# PLC_NPN-16.net
KiCad netlist of a schematic drawn in Altium Designer
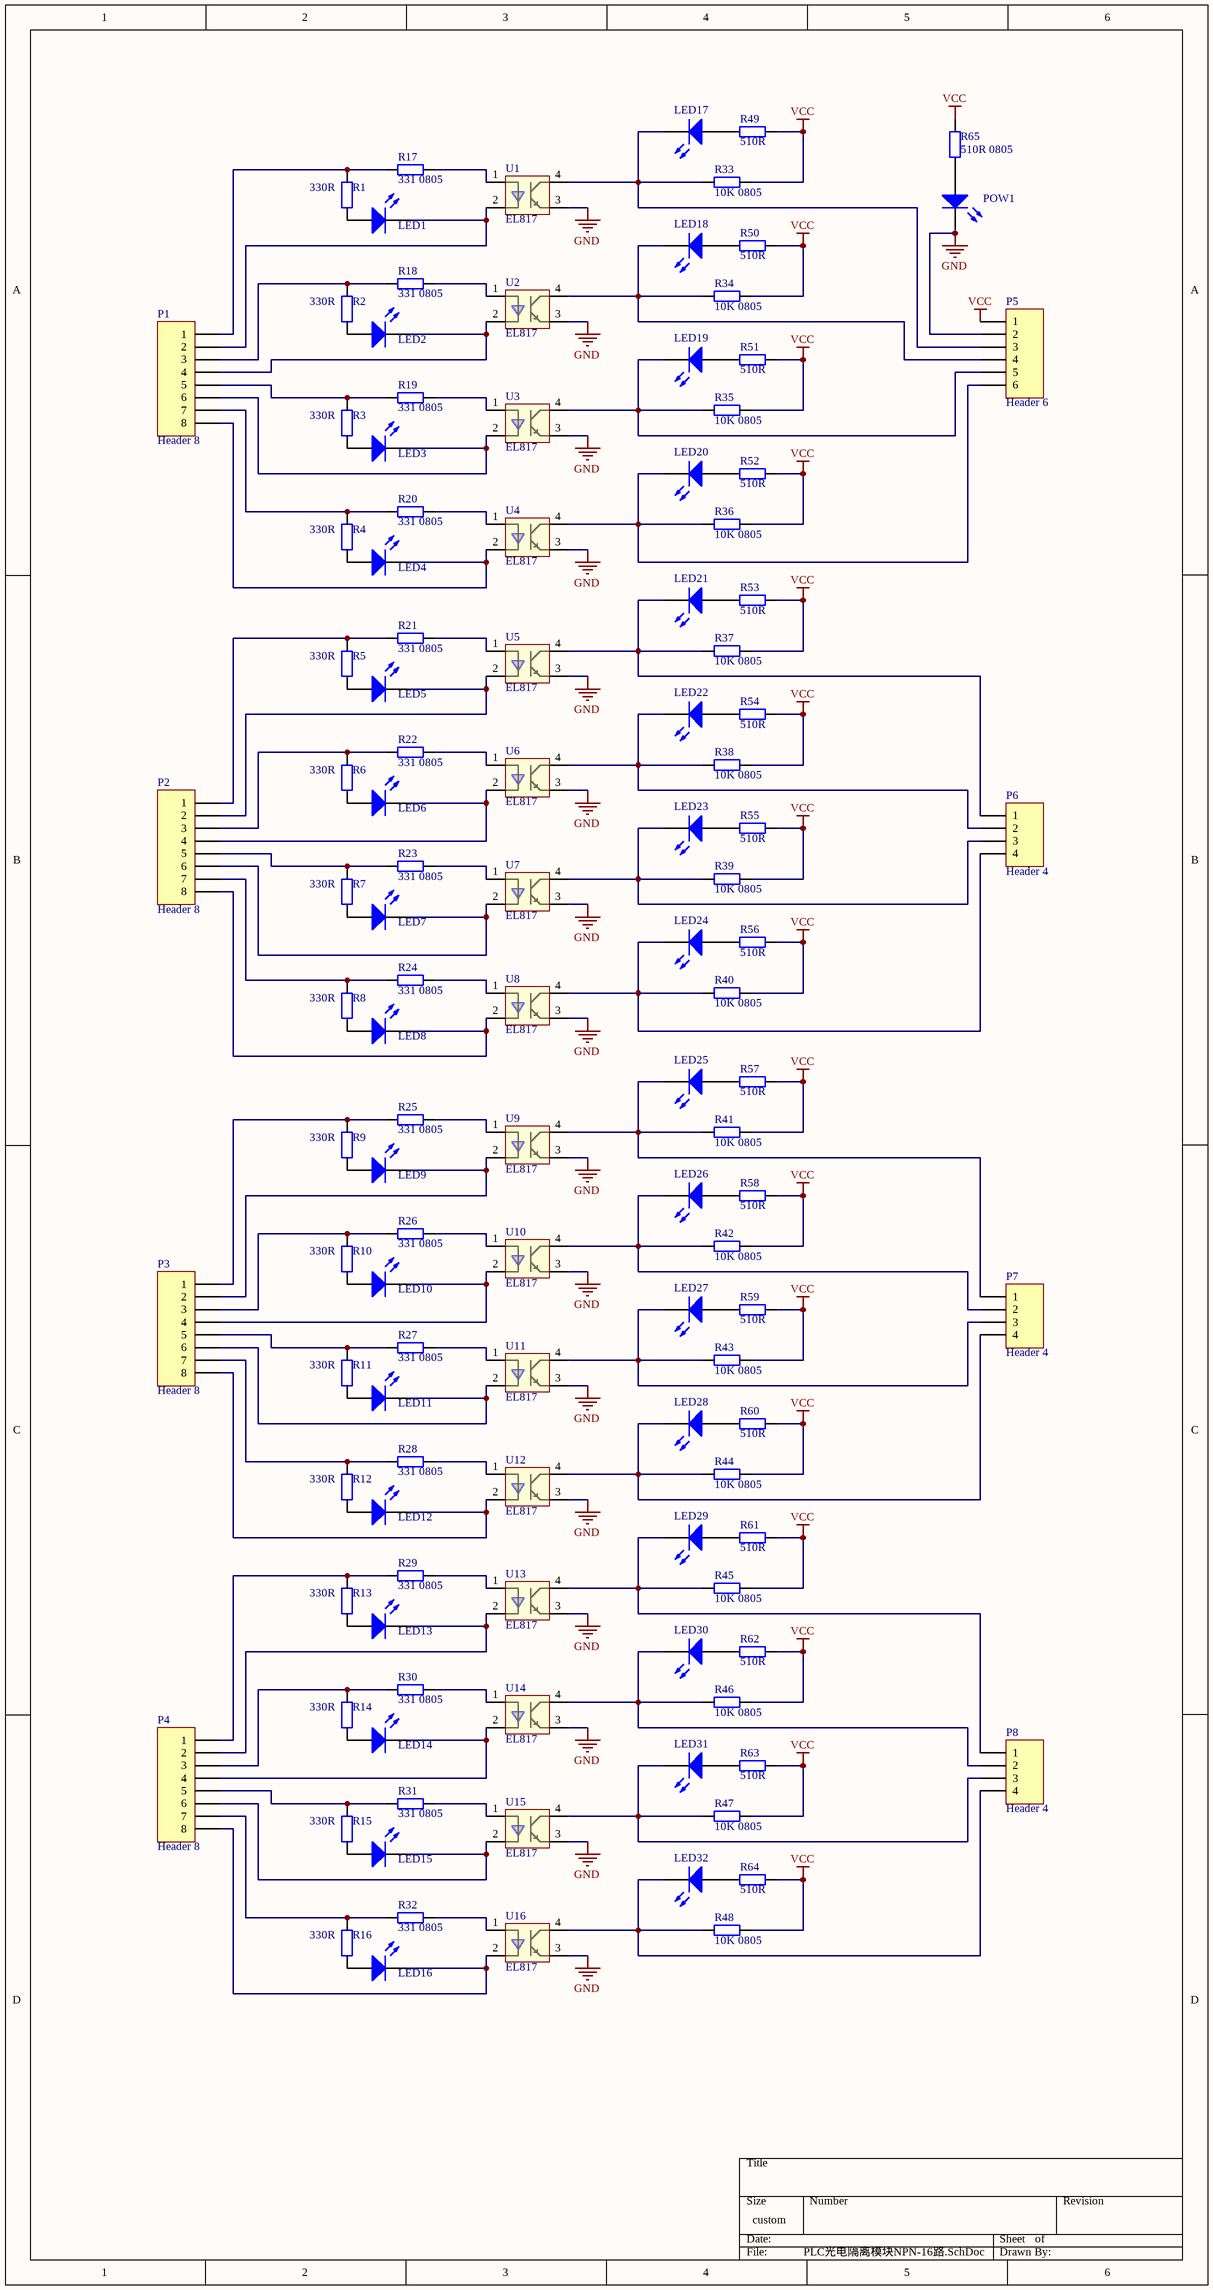
[diagram p0: PLC光电隔离模块NPN-16路.SchDoc]

(export (version "E")
  (design (tool "Eeschema 10.0.6"))
  (components
    (comp (ref "LED1")
      (value "0805")
      (footprint "LC-0805")
      (description "Typical INFRARED GaAs LED")
      (fields (field (name "PUBLISHER") "Altium Limited"))
      (libsource (lib "Miscellaneous Devices") (part "LED0"))
    )
    (comp (ref "LED2")
      (value "0805")
      (footprint "LC-0805")
      (description "Typical INFRARED GaAs LED")
      (fields (field (name "PUBLISHER") "Altium Limited"))
      (libsource (lib "Miscellaneous Devices") (part "LED0"))
    )
    (comp (ref "LED3")
      (value "0805")
      (footprint "LC-0805")
      (description "Typical INFRARED GaAs LED")
      (fields (field (name "PUBLISHER") "Altium Limited"))
      (libsource (lib "Miscellaneous Devices") (part "LED0"))
    )
    (comp (ref "LED4")
      (value "0805")
      (footprint "LC-0805")
      (description "Typical INFRARED GaAs LED")
      (fields (field (name "PUBLISHER") "Altium Limited"))
      (libsource (lib "Miscellaneous Devices") (part "LED0"))
    )
    (comp (ref "LED5")
      (value "0805")
      (footprint "LC-0805")
      (description "Typical INFRARED GaAs LED")
      (fields (field (name "PUBLISHER") "Altium Limited"))
      (libsource (lib "Miscellaneous Devices") (part "LED0"))
    )
    (comp (ref "LED6")
      (value "0805")
      (footprint "LC-0805")
      (description "Typical INFRARED GaAs LED")
      (fields (field (name "PUBLISHER") "Altium Limited"))
      (libsource (lib "Miscellaneous Devices") (part "LED0"))
    )
    (comp (ref "LED7")
      (value "0805")
      (footprint "LC-0805")
      (description "Typical INFRARED GaAs LED")
      (fields (field (name "PUBLISHER") "Altium Limited"))
      (libsource (lib "Miscellaneous Devices") (part "LED0"))
    )
    (comp (ref "LED8")
      (value "0805")
      (footprint "LC-0805")
      (description "Typical INFRARED GaAs LED")
      (fields (field (name "PUBLISHER") "Altium Limited"))
      (libsource (lib "Miscellaneous Devices") (part "LED0"))
    )
    (comp (ref "LED9")
      (value "0805")
      (footprint "LC-0805")
      (description "Typical INFRARED GaAs LED")
      (fields (field (name "PUBLISHER") "Altium Limited"))
      (libsource (lib "Miscellaneous Devices") (part "LED0"))
    )
    (comp (ref "LED10")
      (value "0805")
      (footprint "LC-0805")
      (description "Typical INFRARED GaAs LED")
      (fields (field (name "PUBLISHER") "Altium Limited"))
      (libsource (lib "Miscellaneous Devices") (part "LED0"))
    )
    (comp (ref "LED11")
      (value "0805")
      (footprint "LC-0805")
      (description "Typical INFRARED GaAs LED")
      (fields (field (name "PUBLISHER") "Altium Limited"))
      (libsource (lib "Miscellaneous Devices") (part "LED0"))
    )
    (comp (ref "LED12")
      (value "0805")
      (footprint "LC-0805")
      (description "Typical INFRARED GaAs LED")
      (fields (field (name "PUBLISHER") "Altium Limited"))
      (libsource (lib "Miscellaneous Devices") (part "LED0"))
    )
    (comp (ref "LED13")
      (value "0805")
      (footprint "LC-0805")
      (description "Typical INFRARED GaAs LED")
      (fields (field (name "PUBLISHER") "Altium Limited"))
      (libsource (lib "Miscellaneous Devices") (part "LED0"))
    )
    (comp (ref "LED14")
      (value "0805")
      (footprint "LC-0805")
      (description "Typical INFRARED GaAs LED")
      (fields (field (name "PUBLISHER") "Altium Limited"))
      (libsource (lib "Miscellaneous Devices") (part "LED0"))
    )
    (comp (ref "LED15")
      (value "0805")
      (footprint "LC-0805")
      (description "Typical INFRARED GaAs LED")
      (fields (field (name "PUBLISHER") "Altium Limited"))
      (libsource (lib "Miscellaneous Devices") (part "LED0"))
    )
    (comp (ref "LED16")
      (value "0805")
      (footprint "LC-0805")
      (description "Typical INFRARED GaAs LED")
      (fields (field (name "PUBLISHER") "Altium Limited"))
      (libsource (lib "Miscellaneous Devices") (part "LED0"))
    )
    (comp (ref "LED17")
      (value "0805")
      (footprint "LC-0805")
      (description "Typical INFRARED GaAs LED")
      (fields (field (name "PUBLISHER") "Altium Limited"))
      (libsource (lib "Miscellaneous Devices") (part "LED0"))
    )
    (comp (ref "LED18")
      (value "0805")
      (footprint "LC-0805")
      (description "Typical INFRARED GaAs LED")
      (fields (field (name "PUBLISHER") "Altium Limited"))
      (libsource (lib "Miscellaneous Devices") (part "LED0"))
    )
    (comp (ref "LED19")
      (value "0805")
      (footprint "LC-0805")
      (description "Typical INFRARED GaAs LED")
      (fields (field (name "PUBLISHER") "Altium Limited"))
      (libsource (lib "Miscellaneous Devices") (part "LED0"))
    )
    (comp (ref "LED20")
      (value "0805")
      (footprint "LC-0805")
      (description "Typical INFRARED GaAs LED")
      (fields (field (name "PUBLISHER") "Altium Limited"))
      (libsource (lib "Miscellaneous Devices") (part "LED0"))
    )
    (comp (ref "LED21")
      (value "0805")
      (footprint "LC-0805")
      (description "Typical INFRARED GaAs LED")
      (fields (field (name "PUBLISHER") "Altium Limited"))
      (libsource (lib "Miscellaneous Devices") (part "LED0"))
    )
    (comp (ref "LED22")
      (value "0805")
      (footprint "LC-0805")
      (description "Typical INFRARED GaAs LED")
      (fields (field (name "PUBLISHER") "Altium Limited"))
      (libsource (lib "Miscellaneous Devices") (part "LED0"))
    )
    (comp (ref "LED23")
      (value "0805")
      (footprint "LC-0805")
      (description "Typical INFRARED GaAs LED")
      (fields (field (name "PUBLISHER") "Altium Limited"))
      (libsource (lib "Miscellaneous Devices") (part "LED0"))
    )
    (comp (ref "LED24")
      (value "0805")
      (footprint "LC-0805")
      (description "Typical INFRARED GaAs LED")
      (fields (field (name "PUBLISHER") "Altium Limited"))
      (libsource (lib "Miscellaneous Devices") (part "LED0"))
    )
    (comp (ref "LED25")
      (value "0805")
      (footprint "LC-0805")
      (description "Typical INFRARED GaAs LED")
      (fields (field (name "PUBLISHER") "Altium Limited"))
      (libsource (lib "Miscellaneous Devices") (part "LED0"))
    )
    (comp (ref "LED26")
      (value "0805")
      (footprint "LC-0805")
      (description "Typical INFRARED GaAs LED")
      (fields (field (name "PUBLISHER") "Altium Limited"))
      (libsource (lib "Miscellaneous Devices") (part "LED0"))
    )
    (comp (ref "LED27")
      (value "0805")
      (footprint "LC-0805")
      (description "Typical INFRARED GaAs LED")
      (fields (field (name "PUBLISHER") "Altium Limited"))
      (libsource (lib "Miscellaneous Devices") (part "LED0"))
    )
    (comp (ref "LED28")
      (value "0805")
      (footprint "LC-0805")
      (description "Typical INFRARED GaAs LED")
      (fields (field (name "PUBLISHER") "Altium Limited"))
      (libsource (lib "Miscellaneous Devices") (part "LED0"))
    )
    (comp (ref "LED29")
      (value "0805")
      (footprint "LC-0805")
      (description "Typical INFRARED GaAs LED")
      (fields (field (name "PUBLISHER") "Altium Limited"))
      (libsource (lib "Miscellaneous Devices") (part "LED0"))
    )
    (comp (ref "LED30")
      (value "0805")
      (footprint "LC-0805")
      (description "Typical INFRARED GaAs LED")
      (fields (field (name "PUBLISHER") "Altium Limited"))
      (libsource (lib "Miscellaneous Devices") (part "LED0"))
    )
    (comp (ref "LED31")
      (value "0805")
      (footprint "LC-0805")
      (description "Typical INFRARED GaAs LED")
      (fields (field (name "PUBLISHER") "Altium Limited"))
      (libsource (lib "Miscellaneous Devices") (part "LED0"))
    )
    (comp (ref "LED32")
      (value "0805")
      (footprint "LC-0805")
      (description "Typical INFRARED GaAs LED")
      (fields (field (name "PUBLISHER") "Altium Limited"))
      (libsource (lib "Miscellaneous Devices") (part "LED0"))
    )
    (comp (ref "P1")
      (value "Header 8")
      (footprint "128单排8位端子5.08")
      (description "Header, 8-Pin")
      (fields (field (name "PUBLISHER") "Altium Limited"))
      (libsource (lib "Miscellaneous Connectors") (part "Header 8"))
    )
    (comp (ref "P2")
      (value "Header 8")
      (footprint "128单排8位端子5.08")
      (description "Header, 8-Pin")
      (fields (field (name "PUBLISHER") "Altium Limited"))
      (libsource (lib "Miscellaneous Connectors") (part "Header 8"))
    )
    (comp (ref "P3")
      (value "Header 8")
      (footprint "128单排8位端子5.08")
      (description "Header, 8-Pin")
      (fields (field (name "PUBLISHER") "Altium Limited"))
      (libsource (lib "Miscellaneous Connectors") (part "Header 8"))
    )
    (comp (ref "P4")
      (value "Header 8")
      (footprint "128单排8位端子5.08")
      (description "Header, 8-Pin")
      (fields (field (name "PUBLISHER") "Altium Limited"))
      (libsource (lib "Miscellaneous Connectors") (part "Header 8"))
    )
    (comp (ref "P5")
      (value "Header 6")
      (footprint "128单排6位端子5.08 - 反向")
      (description "Header, 6-Pin")
      (fields (field (name "PUBLISHER") "Altium Limited"))
      (libsource (lib "Miscellaneous Connectors") (part "Header 6"))
    )
    (comp (ref "P6")
      (value "Header 4")
      (footprint "128单排4位端子5.08")
      (description "Header, 4-Pin")
      (fields (field (name "PUBLISHER") "Altium Limited"))
      (libsource (lib "Miscellaneous Connectors") (part "Header 4"))
    )
    (comp (ref "P7")
      (value "Header 4")
      (footprint "128单排4位端子5.08")
      (description "Header, 4-Pin")
      (fields (field (name "PUBLISHER") "Altium Limited"))
      (libsource (lib "Miscellaneous Connectors") (part "Header 4"))
    )
    (comp (ref "P8")
      (value "Header 4")
      (footprint "128单排4位端子5.08")
      (description "Header, 4-Pin")
      (fields (field (name "PUBLISHER") "Altium Limited"))
      (libsource (lib "Miscellaneous Connectors") (part "Header 4"))
    )
    (comp (ref "POW1")
      (value "0805")
      (footprint "LC-0805")
      (description "Typical INFRARED GaAs LED")
      (fields (field (name "PUBLISHER") "Altium Limited"))
      (libsource (lib "Miscellaneous Devices") (part "LED0"))
    )
    (comp (ref "R1")
      (value "330R")
      (footprint "LC-0805_L")
      (description "Resistor")
      (fields (field (name "PUBLISHER") "Altium Limited"))
      (libsource (lib "") (part "Res2_2"))
    )
    (comp (ref "R2")
      (value "330R")
      (footprint "LC-0805_L")
      (description "Resistor")
      (fields (field (name "PUBLISHER") "Altium Limited"))
      (libsource (lib "") (part "Res2_2"))
    )
    (comp (ref "R3")
      (value "330R")
      (footprint "LC-0805_L")
      (description "Resistor")
      (fields (field (name "PUBLISHER") "Altium Limited"))
      (libsource (lib "") (part "Res2_2"))
    )
    (comp (ref "R4")
      (value "330R")
      (footprint "LC-0805_L")
      (description "Resistor")
      (fields (field (name "PUBLISHER") "Altium Limited"))
      (libsource (lib "") (part "Res2_2"))
    )
    (comp (ref "R5")
      (value "330R")
      (footprint "LC-0805_L")
      (description "Resistor")
      (fields (field (name "PUBLISHER") "Altium Limited"))
      (libsource (lib "") (part "Res2_2"))
    )
    (comp (ref "R6")
      (value "330R")
      (footprint "LC-0805_L")
      (description "Resistor")
      (fields (field (name "PUBLISHER") "Altium Limited"))
      (libsource (lib "") (part "Res2_2"))
    )
    (comp (ref "R7")
      (value "330R")
      (footprint "LC-0805_L")
      (description "Resistor")
      (fields (field (name "PUBLISHER") "Altium Limited"))
      (libsource (lib "") (part "Res2_2"))
    )
    (comp (ref "R8")
      (value "330R")
      (footprint "LC-0805_L")
      (description "Resistor")
      (fields (field (name "PUBLISHER") "Altium Limited"))
      (libsource (lib "") (part "Res2_2"))
    )
    (comp (ref "R9")
      (value "330R")
      (footprint "LC-0805_L")
      (description "Resistor")
      (fields (field (name "PUBLISHER") "Altium Limited"))
      (libsource (lib "") (part "Res2_2"))
    )
    (comp (ref "R10")
      (value "330R")
      (footprint "LC-0805_L")
      (description "Resistor")
      (fields (field (name "PUBLISHER") "Altium Limited"))
      (libsource (lib "") (part "Res2_2"))
    )
    (comp (ref "R11")
      (value "330R")
      (footprint "LC-0805_L")
      (description "Resistor")
      (fields (field (name "PUBLISHER") "Altium Limited"))
      (libsource (lib "") (part "Res2_2"))
    )
    (comp (ref "R12")
      (value "330R")
      (footprint "LC-0805_L")
      (description "Resistor")
      (fields (field (name "PUBLISHER") "Altium Limited"))
      (libsource (lib "") (part "Res2_2"))
    )
    (comp (ref "R13")
      (value "330R")
      (footprint "LC-0805_L")
      (description "Resistor")
      (fields (field (name "PUBLISHER") "Altium Limited"))
      (libsource (lib "") (part "Res2_2"))
    )
    (comp (ref "R14")
      (value "330R")
      (footprint "LC-0805_L")
      (description "Resistor")
      (fields (field (name "PUBLISHER") "Altium Limited"))
      (libsource (lib "") (part "Res2_2"))
    )
    (comp (ref "R15")
      (value "330R")
      (footprint "LC-0805_L")
      (description "Resistor")
      (fields (field (name "PUBLISHER") "Altium Limited"))
      (libsource (lib "") (part "Res2_2"))
    )
    (comp (ref "R16")
      (value "330R")
      (footprint "LC-0805_L")
      (description "Resistor")
      (fields (field (name "PUBLISHER") "Altium Limited"))
      (libsource (lib "") (part "Res2_2"))
    )
    (comp (ref "R17")
      (value "331 0805")
      (footprint "LC-0805_L")
      (description "Resistor")
      (fields (field (name "PUBLISHER") "Altium Limited"))
      (libsource (lib "Miscellaneous Devices") (part "Res2"))
    )
    (comp (ref "R18")
      (value "331 0805")
      (footprint "LC-0805_L")
      (description "Resistor")
      (fields (field (name "PUBLISHER") "Altium Limited"))
      (libsource (lib "Miscellaneous Devices") (part "Res2"))
    )
    (comp (ref "R19")
      (value "331 0805")
      (footprint "LC-0805_L")
      (description "Resistor")
      (fields (field (name "PUBLISHER") "Altium Limited"))
      (libsource (lib "Miscellaneous Devices") (part "Res2"))
    )
    (comp (ref "R20")
      (value "331 0805")
      (footprint "LC-0805_L")
      (description "Resistor")
      (fields (field (name "PUBLISHER") "Altium Limited"))
      (libsource (lib "Miscellaneous Devices") (part "Res2"))
    )
    (comp (ref "R21")
      (value "331 0805")
      (footprint "LC-0805_L")
      (description "Resistor")
      (fields (field (name "PUBLISHER") "Altium Limited"))
      (libsource (lib "Miscellaneous Devices") (part "Res2"))
    )
    (comp (ref "R22")
      (value "331 0805")
      (footprint "LC-0805_L")
      (description "Resistor")
      (fields (field (name "PUBLISHER") "Altium Limited"))
      (libsource (lib "Miscellaneous Devices") (part "Res2"))
    )
    (comp (ref "R23")
      (value "331 0805")
      (footprint "LC-0805_L")
      (description "Resistor")
      (fields (field (name "PUBLISHER") "Altium Limited"))
      (libsource (lib "Miscellaneous Devices") (part "Res2"))
    )
    (comp (ref "R24")
      (value "331 0805")
      (footprint "LC-0805_L")
      (description "Resistor")
      (fields (field (name "PUBLISHER") "Altium Limited"))
      (libsource (lib "Miscellaneous Devices") (part "Res2"))
    )
    (comp (ref "R25")
      (value "331 0805")
      (footprint "LC-0805_L")
      (description "Resistor")
      (fields (field (name "PUBLISHER") "Altium Limited"))
      (libsource (lib "Miscellaneous Devices") (part "Res2"))
    )
    (comp (ref "R26")
      (value "331 0805")
      (footprint "LC-0805_L")
      (description "Resistor")
      (fields (field (name "PUBLISHER") "Altium Limited"))
      (libsource (lib "Miscellaneous Devices") (part "Res2"))
    )
    (comp (ref "R27")
      (value "331 0805")
      (footprint "LC-0805_L")
      (description "Resistor")
      (fields (field (name "PUBLISHER") "Altium Limited"))
      (libsource (lib "Miscellaneous Devices") (part "Res2"))
    )
    (comp (ref "R28")
      (value "331 0805")
      (footprint "LC-0805_L")
      (description "Resistor")
      (fields (field (name "PUBLISHER") "Altium Limited"))
      (libsource (lib "Miscellaneous Devices") (part "Res2"))
    )
    (comp (ref "R29")
      (value "331 0805")
      (footprint "LC-0805_L")
      (description "Resistor")
      (fields (field (name "PUBLISHER") "Altium Limited"))
      (libsource (lib "Miscellaneous Devices") (part "Res2"))
    )
    (comp (ref "R30")
      (value "331 0805")
      (footprint "LC-0805_L")
      (description "Resistor")
      (fields (field (name "PUBLISHER") "Altium Limited"))
      (libsource (lib "Miscellaneous Devices") (part "Res2"))
    )
    (comp (ref "R31")
      (value "331 0805")
      (footprint "LC-0805_L")
      (description "Resistor")
      (fields (field (name "PUBLISHER") "Altium Limited"))
      (libsource (lib "Miscellaneous Devices") (part "Res2"))
    )
    (comp (ref "R32")
      (value "331 0805")
      (footprint "LC-0805_L")
      (description "Resistor")
      (fields (field (name "PUBLISHER") "Altium Limited"))
      (libsource (lib "Miscellaneous Devices") (part "Res2"))
    )
    (comp (ref "R33")
      (value "10K 0805")
      (footprint "LC-0805_L")
      (description "Resistor")
      (fields (field (name "PUBLISHER") "Altium Limited"))
      (libsource (lib "Miscellaneous Devices") (part "Res2"))
    )
    (comp (ref "R34")
      (value "10K 0805")
      (footprint "LC-0805_L")
      (description "Resistor")
      (fields (field (name "PUBLISHER") "Altium Limited"))
      (libsource (lib "Miscellaneous Devices") (part "Res2"))
    )
    (comp (ref "R35")
      (value "10K 0805")
      (footprint "LC-0805_L")
      (description "Resistor")
      (fields (field (name "PUBLISHER") "Altium Limited"))
      (libsource (lib "Miscellaneous Devices") (part "Res2"))
    )
    (comp (ref "R36")
      (value "10K 0805")
      (footprint "LC-0805_L")
      (description "Resistor")
      (fields (field (name "PUBLISHER") "Altium Limited"))
      (libsource (lib "Miscellaneous Devices") (part "Res2"))
    )
    (comp (ref "R37")
      (value "10K 0805")
      (footprint "LC-0805_L")
      (description "Resistor")
      (fields (field (name "PUBLISHER") "Altium Limited"))
      (libsource (lib "Miscellaneous Devices") (part "Res2"))
    )
    (comp (ref "R38")
      (value "10K 0805")
      (footprint "LC-0805_L")
      (description "Resistor")
      (fields (field (name "PUBLISHER") "Altium Limited"))
      (libsource (lib "Miscellaneous Devices") (part "Res2"))
    )
    (comp (ref "R39")
      (value "10K 0805")
      (footprint "LC-0805_L")
      (description "Resistor")
      (fields (field (name "PUBLISHER") "Altium Limited"))
      (libsource (lib "Miscellaneous Devices") (part "Res2"))
    )
    (comp (ref "R40")
      (value "10K 0805")
      (footprint "LC-0805_L")
      (description "Resistor")
      (fields (field (name "PUBLISHER") "Altium Limited"))
      (libsource (lib "Miscellaneous Devices") (part "Res2"))
    )
    (comp (ref "R41")
      (value "10K 0805")
      (footprint "LC-0805_L")
      (description "Resistor")
      (fields (field (name "PUBLISHER") "Altium Limited"))
      (libsource (lib "Miscellaneous Devices") (part "Res2"))
    )
    (comp (ref "R42")
      (value "10K 0805")
      (footprint "LC-0805_L")
      (description "Resistor")
      (fields (field (name "PUBLISHER") "Altium Limited"))
      (libsource (lib "Miscellaneous Devices") (part "Res2"))
    )
    (comp (ref "R43")
      (value "10K 0805")
      (footprint "LC-0805_L")
      (description "Resistor")
      (fields (field (name "PUBLISHER") "Altium Limited"))
      (libsource (lib "Miscellaneous Devices") (part "Res2"))
    )
    (comp (ref "R44")
      (value "10K 0805")
      (footprint "LC-0805_L")
      (description "Resistor")
      (fields (field (name "PUBLISHER") "Altium Limited"))
      (libsource (lib "Miscellaneous Devices") (part "Res2"))
    )
    (comp (ref "R45")
      (value "10K 0805")
      (footprint "LC-0805_L")
      (description "Resistor")
      (fields (field (name "PUBLISHER") "Altium Limited"))
      (libsource (lib "Miscellaneous Devices") (part "Res2"))
    )
    (comp (ref "R46")
      (value "10K 0805")
      (footprint "LC-0805_L")
      (description "Resistor")
      (fields (field (name "PUBLISHER") "Altium Limited"))
      (libsource (lib "Miscellaneous Devices") (part "Res2"))
    )
    (comp (ref "R47")
      (value "10K 0805")
      (footprint "LC-0805_L")
      (description "Resistor")
      (fields (field (name "PUBLISHER") "Altium Limited"))
      (libsource (lib "Miscellaneous Devices") (part "Res2"))
    )
    (comp (ref "R48")
      (value "10K 0805")
      (footprint "LC-0805_L")
      (description "Resistor")
      (fields (field (name "PUBLISHER") "Altium Limited"))
      (libsource (lib "Miscellaneous Devices") (part "Res2"))
    )
    (comp (ref "R49")
      (value "510R")
      (footprint "LC-0805_L")
      (description "Resistor")
      (fields (field (name "PUBLISHER") "Altium Limited"))
      (libsource (lib "") (part "Res2_1"))
    )
    (comp (ref "R50")
      (value "510R")
      (footprint "LC-0805_L")
      (description "Resistor")
      (fields (field (name "PUBLISHER") "Altium Limited"))
      (libsource (lib "") (part "Res2_1"))
    )
    (comp (ref "R51")
      (value "510R")
      (footprint "LC-0805_L")
      (description "Resistor")
      (fields (field (name "PUBLISHER") "Altium Limited"))
      (libsource (lib "") (part "Res2_1"))
    )
    (comp (ref "R52")
      (value "510R")
      (footprint "LC-0805_L")
      (description "Resistor")
      (fields (field (name "PUBLISHER") "Altium Limited"))
      (libsource (lib "") (part "Res2_1"))
    )
    (comp (ref "R53")
      (value "510R")
      (footprint "LC-0805_L")
      (description "Resistor")
      (fields (field (name "PUBLISHER") "Altium Limited"))
      (libsource (lib "") (part "Res2_1"))
    )
    (comp (ref "R54")
      (value "510R")
      (footprint "LC-0805_L")
      (description "Resistor")
      (fields (field (name "PUBLISHER") "Altium Limited"))
      (libsource (lib "") (part "Res2_1"))
    )
    (comp (ref "R55")
      (value "510R")
      (footprint "LC-0805_L")
      (description "Resistor")
      (fields (field (name "PUBLISHER") "Altium Limited"))
      (libsource (lib "") (part "Res2_1"))
    )
    (comp (ref "R56")
      (value "510R")
      (footprint "LC-0805_L")
      (description "Resistor")
      (fields (field (name "PUBLISHER") "Altium Limited"))
      (libsource (lib "") (part "Res2_1"))
    )
    (comp (ref "R57")
      (value "510R")
      (footprint "LC-0805_L")
      (description "Resistor")
      (fields (field (name "PUBLISHER") "Altium Limited"))
      (libsource (lib "") (part "Res2_1"))
    )
    (comp (ref "R58")
      (value "510R")
      (footprint "LC-0805_L")
      (description "Resistor")
      (fields (field (name "PUBLISHER") "Altium Limited"))
      (libsource (lib "") (part "Res2_1"))
    )
    (comp (ref "R59")
      (value "510R")
      (footprint "LC-0805_L")
      (description "Resistor")
      (fields (field (name "PUBLISHER") "Altium Limited"))
      (libsource (lib "") (part "Res2_1"))
    )
    (comp (ref "R60")
      (value "510R")
      (footprint "LC-0805_L")
      (description "Resistor")
      (fields (field (name "PUBLISHER") "Altium Limited"))
      (libsource (lib "") (part "Res2_1"))
    )
    (comp (ref "R61")
      (value "510R")
      (footprint "LC-0805_L")
      (description "Resistor")
      (fields (field (name "PUBLISHER") "Altium Limited"))
      (libsource (lib "") (part "Res2_1"))
    )
    (comp (ref "R62")
      (value "510R")
      (footprint "LC-0805_L")
      (description "Resistor")
      (fields (field (name "PUBLISHER") "Altium Limited"))
      (libsource (lib "") (part "Res2_1"))
    )
    (comp (ref "R63")
      (value "510R")
      (footprint "LC-0805_L")
      (description "Resistor")
      (fields (field (name "PUBLISHER") "Altium Limited"))
      (libsource (lib "") (part "Res2_1"))
    )
    (comp (ref "R64")
      (value "510R")
      (footprint "LC-0805_L")
      (description "Resistor")
      (fields (field (name "PUBLISHER") "Altium Limited"))
      (libsource (lib "") (part "Res2_1"))
    )
    (comp (ref "R65")
      (value "510R 0805")
      (footprint "LC-0805_L")
      (description "Resistor")
      (fields (field (name "PUBLISHER") "Altium Limited"))
      (libsource (lib "") (part "Res2_2"))
    )
    (comp (ref "U1") (value "EL817") (footprint "EL817") (libsource (lib "我的原理图库") (part "EL817")))
    (comp (ref "U2") (value "EL817") (footprint "EL817") (libsource (lib "我的原理图库") (part "EL817")))
    (comp (ref "U3") (value "EL817") (footprint "EL817") (libsource (lib "我的原理图库") (part "EL817")))
    (comp (ref "U4") (value "EL817") (footprint "EL817") (libsource (lib "我的原理图库") (part "EL817")))
    (comp (ref "U5") (value "EL817") (footprint "EL817") (libsource (lib "我的原理图库") (part "EL817")))
    (comp (ref "U6") (value "EL817") (footprint "EL817") (libsource (lib "我的原理图库") (part "EL817")))
    (comp (ref "U7") (value "EL817") (footprint "EL817") (libsource (lib "我的原理图库") (part "EL817")))
    (comp (ref "U8") (value "EL817") (footprint "EL817") (libsource (lib "我的原理图库") (part "EL817")))
    (comp (ref "U9") (value "EL817") (footprint "EL817") (libsource (lib "我的原理图库") (part "EL817")))
    (comp (ref "U10") (value "EL817") (footprint "EL817") (libsource (lib "我的原理图库") (part "EL817")))
    (comp (ref "U11") (value "EL817") (footprint "EL817") (libsource (lib "我的原理图库") (part "EL817")))
    (comp (ref "U12") (value "EL817") (footprint "EL817") (libsource (lib "我的原理图库") (part "EL817")))
    (comp (ref "U13") (value "EL817") (footprint "EL817") (libsource (lib "我的原理图库") (part "EL817")))
    (comp (ref "U14") (value "EL817") (footprint "EL817") (libsource (lib "我的原理图库") (part "EL817")))
    (comp (ref "U15") (value "EL817") (footprint "EL817") (libsource (lib "我的原理图库") (part "EL817")))
    (comp (ref "U16") (value "EL817") (footprint "EL817") (libsource (lib "我的原理图库") (part "EL817")))
  )
  (nets
    (net (code "1") (name "GND") (class "Default")
      (node (ref "P5") (pin "2") (pinfunction "2_2") (pintype "passive"))
      (node (ref "POW1") (pin "2") (pinfunction "K_2") (pintype "passive"))
      (node (ref "U1") (pin "3") (pinfunction "3_3") (pintype "passive"))
      (node (ref "U10") (pin "3") (pinfunction "3_3") (pintype "passive"))
      (node (ref "U11") (pin "3") (pinfunction "3_3") (pintype "passive"))
      (node (ref "U12") (pin "3") (pinfunction "3_3") (pintype "passive"))
      (node (ref "U13") (pin "3") (pinfunction "3_3") (pintype "passive"))
      (node (ref "U14") (pin "3") (pinfunction "3_3") (pintype "passive"))
      (node (ref "U15") (pin "3") (pinfunction "3_3") (pintype "passive"))
      (node (ref "U16") (pin "3") (pinfunction "3_3") (pintype "passive"))
      (node (ref "U2") (pin "3") (pinfunction "3_3") (pintype "passive"))
      (node (ref "U3") (pin "3") (pinfunction "3_3") (pintype "passive"))
      (node (ref "U4") (pin "3") (pinfunction "3_3") (pintype "passive"))
      (node (ref "U5") (pin "3") (pinfunction "3_3") (pintype "passive"))
      (node (ref "U6") (pin "3") (pinfunction "3_3") (pintype "passive"))
      (node (ref "U7") (pin "3") (pinfunction "3_3") (pintype "passive"))
      (node (ref "U8") (pin "3") (pinfunction "3_3") (pintype "passive"))
      (node (ref "U9") (pin "3") (pinfunction "3_3") (pintype "passive"))
    )
    (net (code "2") (name "Net-(LED1-A)") (class "Default")
      (node (ref "LED1") (pin "1") (pinfunction "A_1") (pintype "passive"))
      (node (ref "R1") (pin "1") (pinfunction "1_1") (pintype "passive"))
    )
    (net (code "3") (name "Net-(LED1-K)") (class "Default")
      (node (ref "LED1") (pin "2") (pinfunction "K_2") (pintype "passive"))
      (node (ref "P1") (pin "2") (pinfunction "2_2") (pintype "passive"))
      (node (ref "U1") (pin "2") (pinfunction "2_2") (pintype "passive"))
    )
    (net (code "4") (name "Net-(LED2-A)") (class "Default")
      (node (ref "LED2") (pin "1") (pinfunction "A_1") (pintype "passive"))
      (node (ref "R2") (pin "1") (pinfunction "1_1") (pintype "passive"))
    )
    (net (code "5") (name "Net-(LED2-K)") (class "Default")
      (node (ref "LED2") (pin "2") (pinfunction "K_2") (pintype "passive"))
      (node (ref "P1") (pin "4") (pinfunction "4_4") (pintype "passive"))
      (node (ref "U2") (pin "2") (pinfunction "2_2") (pintype "passive"))
    )
    (net (code "6") (name "Net-(LED3-A)") (class "Default")
      (node (ref "LED3") (pin "1") (pinfunction "A_1") (pintype "passive"))
      (node (ref "R3") (pin "1") (pinfunction "1_1") (pintype "passive"))
    )
    (net (code "7") (name "Net-(LED3-K)") (class "Default")
      (node (ref "LED3") (pin "2") (pinfunction "K_2") (pintype "passive"))
      (node (ref "P1") (pin "6") (pinfunction "6_6") (pintype "passive"))
      (node (ref "U3") (pin "2") (pinfunction "2_2") (pintype "passive"))
    )
    (net (code "8") (name "Net-(LED4-A)") (class "Default")
      (node (ref "LED4") (pin "1") (pinfunction "A_1") (pintype "passive"))
      (node (ref "R4") (pin "1") (pinfunction "1_1") (pintype "passive"))
    )
    (net (code "9") (name "Net-(LED4-K)") (class "Default")
      (node (ref "LED4") (pin "2") (pinfunction "K_2") (pintype "passive"))
      (node (ref "P1") (pin "8") (pinfunction "8_8") (pintype "passive"))
      (node (ref "U4") (pin "2") (pinfunction "2_2") (pintype "passive"))
    )
    (net (code "10") (name "Net-(LED5-A)") (class "Default")
      (node (ref "LED5") (pin "1") (pinfunction "A_1") (pintype "passive"))
      (node (ref "R5") (pin "1") (pinfunction "1_1") (pintype "passive"))
    )
    (net (code "11") (name "Net-(LED5-K)") (class "Default")
      (node (ref "LED5") (pin "2") (pinfunction "K_2") (pintype "passive"))
      (node (ref "P2") (pin "2") (pinfunction "2_2") (pintype "passive"))
      (node (ref "U5") (pin "2") (pinfunction "2_2") (pintype "passive"))
    )
    (net (code "12") (name "Net-(LED6-A)") (class "Default")
      (node (ref "LED6") (pin "1") (pinfunction "A_1") (pintype "passive"))
      (node (ref "R6") (pin "1") (pinfunction "1_1") (pintype "passive"))
    )
    (net (code "13") (name "Net-(LED6-K)") (class "Default")
      (node (ref "LED6") (pin "2") (pinfunction "K_2") (pintype "passive"))
      (node (ref "P2") (pin "4") (pinfunction "4_4") (pintype "passive"))
      (node (ref "U6") (pin "2") (pinfunction "2_2") (pintype "passive"))
    )
    (net (code "14") (name "Net-(LED7-A)") (class "Default")
      (node (ref "LED7") (pin "1") (pinfunction "A_1") (pintype "passive"))
      (node (ref "R7") (pin "1") (pinfunction "1_1") (pintype "passive"))
    )
    (net (code "15") (name "Net-(LED7-K)") (class "Default")
      (node (ref "LED7") (pin "2") (pinfunction "K_2") (pintype "passive"))
      (node (ref "P2") (pin "6") (pinfunction "6_6") (pintype "passive"))
      (node (ref "U7") (pin "2") (pinfunction "2_2") (pintype "passive"))
    )
    (net (code "16") (name "Net-(LED8-A)") (class "Default")
      (node (ref "LED8") (pin "1") (pinfunction "A_1") (pintype "passive"))
      (node (ref "R8") (pin "1") (pinfunction "1_1") (pintype "passive"))
    )
    (net (code "17") (name "Net-(LED8-K)") (class "Default")
      (node (ref "LED8") (pin "2") (pinfunction "K_2") (pintype "passive"))
      (node (ref "P2") (pin "8") (pinfunction "8_8") (pintype "passive"))
      (node (ref "U8") (pin "2") (pinfunction "2_2") (pintype "passive"))
    )
    (net (code "18") (name "Net-(LED9-A)") (class "Default")
      (node (ref "LED9") (pin "1") (pinfunction "A_1") (pintype "passive"))
      (node (ref "R9") (pin "1") (pinfunction "1_1") (pintype "passive"))
    )
    (net (code "19") (name "Net-(LED9-K)") (class "Default")
      (node (ref "LED9") (pin "2") (pinfunction "K_2") (pintype "passive"))
      (node (ref "P3") (pin "2") (pinfunction "2_2") (pintype "passive"))
      (node (ref "U9") (pin "2") (pinfunction "2_2") (pintype "passive"))
    )
    (net (code "20") (name "Net-(LED10-A)") (class "Default")
      (node (ref "LED10") (pin "1") (pinfunction "A_1") (pintype "passive"))
      (node (ref "R10") (pin "1") (pinfunction "1_1") (pintype "passive"))
    )
    (net (code "21") (name "Net-(LED10-K)") (class "Default")
      (node (ref "LED10") (pin "2") (pinfunction "K_2") (pintype "passive"))
      (node (ref "P3") (pin "4") (pinfunction "4_4") (pintype "passive"))
      (node (ref "U10") (pin "2") (pinfunction "2_2") (pintype "passive"))
    )
    (net (code "22") (name "Net-(LED11-A)") (class "Default")
      (node (ref "LED11") (pin "1") (pinfunction "A_1") (pintype "passive"))
      (node (ref "R11") (pin "1") (pinfunction "1_1") (pintype "passive"))
    )
    (net (code "23") (name "Net-(LED11-K)") (class "Default")
      (node (ref "LED11") (pin "2") (pinfunction "K_2") (pintype "passive"))
      (node (ref "P3") (pin "6") (pinfunction "6_6") (pintype "passive"))
      (node (ref "U11") (pin "2") (pinfunction "2_2") (pintype "passive"))
    )
    (net (code "24") (name "Net-(LED12-A)") (class "Default")
      (node (ref "LED12") (pin "1") (pinfunction "A_1") (pintype "passive"))
      (node (ref "R12") (pin "1") (pinfunction "1_1") (pintype "passive"))
    )
    (net (code "25") (name "Net-(LED12-K)") (class "Default")
      (node (ref "LED12") (pin "2") (pinfunction "K_2") (pintype "passive"))
      (node (ref "P3") (pin "8") (pinfunction "8_8") (pintype "passive"))
      (node (ref "U12") (pin "2") (pinfunction "2_2") (pintype "passive"))
    )
    (net (code "26") (name "Net-(LED13-A)") (class "Default")
      (node (ref "LED13") (pin "1") (pinfunction "A_1") (pintype "passive"))
      (node (ref "R13") (pin "1") (pinfunction "1_1") (pintype "passive"))
    )
    (net (code "27") (name "Net-(LED13-K)") (class "Default")
      (node (ref "LED13") (pin "2") (pinfunction "K_2") (pintype "passive"))
      (node (ref "P4") (pin "2") (pinfunction "2_2") (pintype "passive"))
      (node (ref "U13") (pin "2") (pinfunction "2_2") (pintype "passive"))
    )
    (net (code "28") (name "Net-(LED14-A)") (class "Default")
      (node (ref "LED14") (pin "1") (pinfunction "A_1") (pintype "passive"))
      (node (ref "R14") (pin "1") (pinfunction "1_1") (pintype "passive"))
    )
    (net (code "29") (name "Net-(LED14-K)") (class "Default")
      (node (ref "LED14") (pin "2") (pinfunction "K_2") (pintype "passive"))
      (node (ref "P4") (pin "4") (pinfunction "4_4") (pintype "passive"))
      (node (ref "U14") (pin "2") (pinfunction "2_2") (pintype "passive"))
    )
    (net (code "30") (name "Net-(LED15-A)") (class "Default")
      (node (ref "LED15") (pin "1") (pinfunction "A_1") (pintype "passive"))
      (node (ref "R15") (pin "1") (pinfunction "1_1") (pintype "passive"))
    )
    (net (code "31") (name "Net-(LED15-K)") (class "Default")
      (node (ref "LED15") (pin "2") (pinfunction "K_2") (pintype "passive"))
      (node (ref "P4") (pin "6") (pinfunction "6_6") (pintype "passive"))
      (node (ref "U15") (pin "2") (pinfunction "2_2") (pintype "passive"))
    )
    (net (code "32") (name "Net-(LED16-A)") (class "Default")
      (node (ref "LED16") (pin "1") (pinfunction "A_1") (pintype "passive"))
      (node (ref "R16") (pin "1") (pinfunction "1_1") (pintype "passive"))
    )
    (net (code "33") (name "Net-(LED16-K)") (class "Default")
      (node (ref "LED16") (pin "2") (pinfunction "K_2") (pintype "passive"))
      (node (ref "P4") (pin "8") (pinfunction "8_8") (pintype "passive"))
      (node (ref "U16") (pin "2") (pinfunction "2_2") (pintype "passive"))
    )
    (net (code "34") (name "Net-(LED17-A)") (class "Default")
      (node (ref "LED17") (pin "1") (pinfunction "A_1") (pintype "passive"))
      (node (ref "R49") (pin "2") (pinfunction "2_2") (pintype "passive"))
    )
    (net (code "35") (name "Net-(LED17-K)") (class "Default")
      (node (ref "LED17") (pin "2") (pinfunction "K_2") (pintype "passive"))
      (node (ref "P5") (pin "3") (pinfunction "3_3") (pintype "passive"))
      (node (ref "R33") (pin "1") (pinfunction "1_1") (pintype "passive"))
      (node (ref "U1") (pin "4") (pinfunction "4_4") (pintype "passive"))
    )
    (net (code "36") (name "Net-(LED18-A)") (class "Default")
      (node (ref "LED18") (pin "1") (pinfunction "A_1") (pintype "passive"))
      (node (ref "R50") (pin "2") (pinfunction "2_2") (pintype "passive"))
    )
    (net (code "37") (name "Net-(LED18-K)") (class "Default")
      (node (ref "LED18") (pin "2") (pinfunction "K_2") (pintype "passive"))
      (node (ref "P5") (pin "4") (pinfunction "4_4") (pintype "passive"))
      (node (ref "R34") (pin "1") (pinfunction "1_1") (pintype "passive"))
      (node (ref "U2") (pin "4") (pinfunction "4_4") (pintype "passive"))
    )
    (net (code "38") (name "Net-(LED19-A)") (class "Default")
      (node (ref "LED19") (pin "1") (pinfunction "A_1") (pintype "passive"))
      (node (ref "R51") (pin "2") (pinfunction "2_2") (pintype "passive"))
    )
    (net (code "39") (name "Net-(LED19-K)") (class "Default")
      (node (ref "LED19") (pin "2") (pinfunction "K_2") (pintype "passive"))
      (node (ref "P5") (pin "5") (pinfunction "5_5") (pintype "passive"))
      (node (ref "R35") (pin "1") (pinfunction "1_1") (pintype "passive"))
      (node (ref "U3") (pin "4") (pinfunction "4_4") (pintype "passive"))
    )
    (net (code "40") (name "Net-(LED20-A)") (class "Default")
      (node (ref "LED20") (pin "1") (pinfunction "A_1") (pintype "passive"))
      (node (ref "R52") (pin "2") (pinfunction "2_2") (pintype "passive"))
    )
    (net (code "41") (name "Net-(LED20-K)") (class "Default")
      (node (ref "LED20") (pin "2") (pinfunction "K_2") (pintype "passive"))
      (node (ref "P5") (pin "6") (pinfunction "6_6") (pintype "passive"))
      (node (ref "R36") (pin "1") (pinfunction "1_1") (pintype "passive"))
      (node (ref "U4") (pin "4") (pinfunction "4_4") (pintype "passive"))
    )
    (net (code "42") (name "Net-(LED21-A)") (class "Default")
      (node (ref "LED21") (pin "1") (pinfunction "A_1") (pintype "passive"))
      (node (ref "R53") (pin "2") (pinfunction "2_2") (pintype "passive"))
    )
    (net (code "43") (name "Net-(LED21-K)") (class "Default")
      (node (ref "LED21") (pin "2") (pinfunction "K_2") (pintype "passive"))
      (node (ref "P6") (pin "1") (pinfunction "1_1") (pintype "passive"))
      (node (ref "R37") (pin "1") (pinfunction "1_1") (pintype "passive"))
      (node (ref "U5") (pin "4") (pinfunction "4_4") (pintype "passive"))
    )
    (net (code "44") (name "Net-(LED22-A)") (class "Default")
      (node (ref "LED22") (pin "1") (pinfunction "A_1") (pintype "passive"))
      (node (ref "R54") (pin "2") (pinfunction "2_2") (pintype "passive"))
    )
    (net (code "45") (name "Net-(LED22-K)") (class "Default")
      (node (ref "LED22") (pin "2") (pinfunction "K_2") (pintype "passive"))
      (node (ref "P6") (pin "2") (pinfunction "2_2") (pintype "passive"))
      (node (ref "R38") (pin "1") (pinfunction "1_1") (pintype "passive"))
      (node (ref "U6") (pin "4") (pinfunction "4_4") (pintype "passive"))
    )
    (net (code "46") (name "Net-(LED23-A)") (class "Default")
      (node (ref "LED23") (pin "1") (pinfunction "A_1") (pintype "passive"))
      (node (ref "R55") (pin "2") (pinfunction "2_2") (pintype "passive"))
    )
    (net (code "47") (name "Net-(LED23-K)") (class "Default")
      (node (ref "LED23") (pin "2") (pinfunction "K_2") (pintype "passive"))
      (node (ref "P6") (pin "3") (pinfunction "3_3") (pintype "passive"))
      (node (ref "R39") (pin "1") (pinfunction "1_1") (pintype "passive"))
      (node (ref "U7") (pin "4") (pinfunction "4_4") (pintype "passive"))
    )
    (net (code "48") (name "Net-(LED24-A)") (class "Default")
      (node (ref "LED24") (pin "1") (pinfunction "A_1") (pintype "passive"))
      (node (ref "R56") (pin "2") (pinfunction "2_2") (pintype "passive"))
    )
    (net (code "49") (name "Net-(LED24-K)") (class "Default")
      (node (ref "LED24") (pin "2") (pinfunction "K_2") (pintype "passive"))
      (node (ref "P6") (pin "4") (pinfunction "4_4") (pintype "passive"))
      (node (ref "R40") (pin "1") (pinfunction "1_1") (pintype "passive"))
      (node (ref "U8") (pin "4") (pinfunction "4_4") (pintype "passive"))
    )
    (net (code "50") (name "Net-(LED25-A)") (class "Default")
      (node (ref "LED25") (pin "1") (pinfunction "A_1") (pintype "passive"))
      (node (ref "R57") (pin "2") (pinfunction "2_2") (pintype "passive"))
    )
    (net (code "51") (name "Net-(LED25-K)") (class "Default")
      (node (ref "LED25") (pin "2") (pinfunction "K_2") (pintype "passive"))
      (node (ref "P7") (pin "1") (pinfunction "1_1") (pintype "passive"))
      (node (ref "R41") (pin "1") (pinfunction "1_1") (pintype "passive"))
      (node (ref "U9") (pin "4") (pinfunction "4_4") (pintype "passive"))
    )
    (net (code "52") (name "Net-(LED26-A)") (class "Default")
      (node (ref "LED26") (pin "1") (pinfunction "A_1") (pintype "passive"))
      (node (ref "R58") (pin "2") (pinfunction "2_2") (pintype "passive"))
    )
    (net (code "53") (name "Net-(LED26-K)") (class "Default")
      (node (ref "LED26") (pin "2") (pinfunction "K_2") (pintype "passive"))
      (node (ref "P7") (pin "2") (pinfunction "2_2") (pintype "passive"))
      (node (ref "R42") (pin "1") (pinfunction "1_1") (pintype "passive"))
      (node (ref "U10") (pin "4") (pinfunction "4_4") (pintype "passive"))
    )
    (net (code "54") (name "Net-(LED27-A)") (class "Default")
      (node (ref "LED27") (pin "1") (pinfunction "A_1") (pintype "passive"))
      (node (ref "R59") (pin "2") (pinfunction "2_2") (pintype "passive"))
    )
    (net (code "55") (name "Net-(LED27-K)") (class "Default")
      (node (ref "LED27") (pin "2") (pinfunction "K_2") (pintype "passive"))
      (node (ref "P7") (pin "3") (pinfunction "3_3") (pintype "passive"))
      (node (ref "R43") (pin "1") (pinfunction "1_1") (pintype "passive"))
      (node (ref "U11") (pin "4") (pinfunction "4_4") (pintype "passive"))
    )
    (net (code "56") (name "Net-(LED28-A)") (class "Default")
      (node (ref "LED28") (pin "1") (pinfunction "A_1") (pintype "passive"))
      (node (ref "R60") (pin "2") (pinfunction "2_2") (pintype "passive"))
    )
    (net (code "57") (name "Net-(LED28-K)") (class "Default")
      (node (ref "LED28") (pin "2") (pinfunction "K_2") (pintype "passive"))
      (node (ref "P7") (pin "4") (pinfunction "4_4") (pintype "passive"))
      (node (ref "R44") (pin "1") (pinfunction "1_1") (pintype "passive"))
      (node (ref "U12") (pin "4") (pinfunction "4_4") (pintype "passive"))
    )
    (net (code "58") (name "Net-(LED29-A)") (class "Default")
      (node (ref "LED29") (pin "1") (pinfunction "A_1") (pintype "passive"))
      (node (ref "R61") (pin "2") (pinfunction "2_2") (pintype "passive"))
    )
    (net (code "59") (name "Net-(LED29-K)") (class "Default")
      (node (ref "LED29") (pin "2") (pinfunction "K_2") (pintype "passive"))
      (node (ref "P8") (pin "1") (pinfunction "1_1") (pintype "passive"))
      (node (ref "R45") (pin "1") (pinfunction "1_1") (pintype "passive"))
      (node (ref "U13") (pin "4") (pinfunction "4_4") (pintype "passive"))
    )
    (net (code "60") (name "Net-(LED30-A)") (class "Default")
      (node (ref "LED30") (pin "1") (pinfunction "A_1") (pintype "passive"))
      (node (ref "R62") (pin "2") (pinfunction "2_2") (pintype "passive"))
    )
    (net (code "61") (name "Net-(LED30-K)") (class "Default")
      (node (ref "LED30") (pin "2") (pinfunction "K_2") (pintype "passive"))
      (node (ref "P8") (pin "2") (pinfunction "2_2") (pintype "passive"))
      (node (ref "R46") (pin "1") (pinfunction "1_1") (pintype "passive"))
      (node (ref "U14") (pin "4") (pinfunction "4_4") (pintype "passive"))
    )
    (net (code "62") (name "Net-(LED31-A)") (class "Default")
      (node (ref "LED31") (pin "1") (pinfunction "A_1") (pintype "passive"))
      (node (ref "R63") (pin "2") (pinfunction "2_2") (pintype "passive"))
    )
    (net (code "63") (name "Net-(LED31-K)") (class "Default")
      (node (ref "LED31") (pin "2") (pinfunction "K_2") (pintype "passive"))
      (node (ref "P8") (pin "3") (pinfunction "3_3") (pintype "passive"))
      (node (ref "R47") (pin "1") (pinfunction "1_1") (pintype "passive"))
      (node (ref "U15") (pin "4") (pinfunction "4_4") (pintype "passive"))
    )
    (net (code "64") (name "Net-(LED32-A)") (class "Default")
      (node (ref "LED32") (pin "1") (pinfunction "A_1") (pintype "passive"))
      (node (ref "R64") (pin "2") (pinfunction "2_2") (pintype "passive"))
    )
    (net (code "65") (name "Net-(LED32-K)") (class "Default")
      (node (ref "LED32") (pin "2") (pinfunction "K_2") (pintype "passive"))
      (node (ref "P8") (pin "4") (pinfunction "4_4") (pintype "passive"))
      (node (ref "R48") (pin "1") (pinfunction "1_1") (pintype "passive"))
      (node (ref "U16") (pin "4") (pinfunction "4_4") (pintype "passive"))
    )
    (net (code "66") (name "Net-(P1-Pad1)") (class "Default")
      (node (ref "P1") (pin "1") (pinfunction "1_1") (pintype "passive"))
      (node (ref "R1") (pin "2") (pinfunction "2_2") (pintype "passive"))
      (node (ref "R17") (pin "1") (pinfunction "1_1") (pintype "passive"))
    )
    (net (code "67") (name "Net-(P1-Pad3)") (class "Default")
      (node (ref "P1") (pin "3") (pinfunction "3_3") (pintype "passive"))
      (node (ref "R18") (pin "1") (pinfunction "1_1") (pintype "passive"))
      (node (ref "R2") (pin "2") (pinfunction "2_2") (pintype "passive"))
    )
    (net (code "68") (name "Net-(P1-Pad5)") (class "Default")
      (node (ref "P1") (pin "5") (pinfunction "5_5") (pintype "passive"))
      (node (ref "R19") (pin "1") (pinfunction "1_1") (pintype "passive"))
      (node (ref "R3") (pin "2") (pinfunction "2_2") (pintype "passive"))
    )
    (net (code "69") (name "Net-(P1-Pad7)") (class "Default")
      (node (ref "P1") (pin "7") (pinfunction "7_7") (pintype "passive"))
      (node (ref "R20") (pin "1") (pinfunction "1_1") (pintype "passive"))
      (node (ref "R4") (pin "2") (pinfunction "2_2") (pintype "passive"))
    )
    (net (code "70") (name "Net-(P2-Pad1)") (class "Default")
      (node (ref "P2") (pin "1") (pinfunction "1_1") (pintype "passive"))
      (node (ref "R21") (pin "1") (pinfunction "1_1") (pintype "passive"))
      (node (ref "R5") (pin "2") (pinfunction "2_2") (pintype "passive"))
    )
    (net (code "71") (name "Net-(P2-Pad3)") (class "Default")
      (node (ref "P2") (pin "3") (pinfunction "3_3") (pintype "passive"))
      (node (ref "R22") (pin "1") (pinfunction "1_1") (pintype "passive"))
      (node (ref "R6") (pin "2") (pinfunction "2_2") (pintype "passive"))
    )
    (net (code "72") (name "Net-(P2-Pad5)") (class "Default")
      (node (ref "P2") (pin "5") (pinfunction "5_5") (pintype "passive"))
      (node (ref "R23") (pin "1") (pinfunction "1_1") (pintype "passive"))
      (node (ref "R7") (pin "2") (pinfunction "2_2") (pintype "passive"))
    )
    (net (code "73") (name "Net-(P2-Pad7)") (class "Default")
      (node (ref "P2") (pin "7") (pinfunction "7_7") (pintype "passive"))
      (node (ref "R24") (pin "1") (pinfunction "1_1") (pintype "passive"))
      (node (ref "R8") (pin "2") (pinfunction "2_2") (pintype "passive"))
    )
    (net (code "74") (name "Net-(P3-Pad1)") (class "Default")
      (node (ref "P3") (pin "1") (pinfunction "1_1") (pintype "passive"))
      (node (ref "R25") (pin "1") (pinfunction "1_1") (pintype "passive"))
      (node (ref "R9") (pin "2") (pinfunction "2_2") (pintype "passive"))
    )
    (net (code "75") (name "Net-(P3-Pad3)") (class "Default")
      (node (ref "P3") (pin "3") (pinfunction "3_3") (pintype "passive"))
      (node (ref "R10") (pin "2") (pinfunction "2_2") (pintype "passive"))
      (node (ref "R26") (pin "1") (pinfunction "1_1") (pintype "passive"))
    )
    (net (code "76") (name "Net-(P3-Pad5)") (class "Default")
      (node (ref "P3") (pin "5") (pinfunction "5_5") (pintype "passive"))
      (node (ref "R11") (pin "2") (pinfunction "2_2") (pintype "passive"))
      (node (ref "R27") (pin "1") (pinfunction "1_1") (pintype "passive"))
    )
    (net (code "77") (name "Net-(P3-Pad7)") (class "Default")
      (node (ref "P3") (pin "7") (pinfunction "7_7") (pintype "passive"))
      (node (ref "R12") (pin "2") (pinfunction "2_2") (pintype "passive"))
      (node (ref "R28") (pin "1") (pinfunction "1_1") (pintype "passive"))
    )
    (net (code "78") (name "Net-(P4-Pad1)") (class "Default")
      (node (ref "P4") (pin "1") (pinfunction "1_1") (pintype "passive"))
      (node (ref "R13") (pin "2") (pinfunction "2_2") (pintype "passive"))
      (node (ref "R29") (pin "1") (pinfunction "1_1") (pintype "passive"))
    )
    (net (code "79") (name "Net-(P4-Pad3)") (class "Default")
      (node (ref "P4") (pin "3") (pinfunction "3_3") (pintype "passive"))
      (node (ref "R14") (pin "2") (pinfunction "2_2") (pintype "passive"))
      (node (ref "R30") (pin "1") (pinfunction "1_1") (pintype "passive"))
    )
    (net (code "80") (name "Net-(P4-Pad5)") (class "Default")
      (node (ref "P4") (pin "5") (pinfunction "5_5") (pintype "passive"))
      (node (ref "R15") (pin "2") (pinfunction "2_2") (pintype "passive"))
      (node (ref "R31") (pin "1") (pinfunction "1_1") (pintype "passive"))
    )
    (net (code "81") (name "Net-(P4-Pad7)") (class "Default")
      (node (ref "P4") (pin "7") (pinfunction "7_7") (pintype "passive"))
      (node (ref "R16") (pin "2") (pinfunction "2_2") (pintype "passive"))
      (node (ref "R32") (pin "1") (pinfunction "1_1") (pintype "passive"))
    )
    (net (code "82") (name "Net-(POW1-A)") (class "Default")
      (node (ref "POW1") (pin "1") (pinfunction "A_1") (pintype "passive"))
      (node (ref "R65") (pin "1") (pinfunction "1_1") (pintype "passive"))
    )
    (net (code "83") (name "Net-(R17-Pad2)") (class "Default")
      (node (ref "R17") (pin "2") (pinfunction "2_2") (pintype "passive"))
      (node (ref "U1") (pin "1") (pinfunction "1_1") (pintype "passive"))
    )
    (net (code "84") (name "Net-(R18-Pad2)") (class "Default")
      (node (ref "R18") (pin "2") (pinfunction "2_2") (pintype "passive"))
      (node (ref "U2") (pin "1") (pinfunction "1_1") (pintype "passive"))
    )
    (net (code "85") (name "Net-(R19-Pad2)") (class "Default")
      (node (ref "R19") (pin "2") (pinfunction "2_2") (pintype "passive"))
      (node (ref "U3") (pin "1") (pinfunction "1_1") (pintype "passive"))
    )
    (net (code "86") (name "Net-(R20-Pad2)") (class "Default")
      (node (ref "R20") (pin "2") (pinfunction "2_2") (pintype "passive"))
      (node (ref "U4") (pin "1") (pinfunction "1_1") (pintype "passive"))
    )
    (net (code "87") (name "Net-(R21-Pad2)") (class "Default")
      (node (ref "R21") (pin "2") (pinfunction "2_2") (pintype "passive"))
      (node (ref "U5") (pin "1") (pinfunction "1_1") (pintype "passive"))
    )
    (net (code "88") (name "Net-(R22-Pad2)") (class "Default")
      (node (ref "R22") (pin "2") (pinfunction "2_2") (pintype "passive"))
      (node (ref "U6") (pin "1") (pinfunction "1_1") (pintype "passive"))
    )
    (net (code "89") (name "Net-(R23-Pad2)") (class "Default")
      (node (ref "R23") (pin "2") (pinfunction "2_2") (pintype "passive"))
      (node (ref "U7") (pin "1") (pinfunction "1_1") (pintype "passive"))
    )
    (net (code "90") (name "Net-(R24-Pad2)") (class "Default")
      (node (ref "R24") (pin "2") (pinfunction "2_2") (pintype "passive"))
      (node (ref "U8") (pin "1") (pinfunction "1_1") (pintype "passive"))
    )
    (net (code "91") (name "Net-(R25-Pad2)") (class "Default")
      (node (ref "R25") (pin "2") (pinfunction "2_2") (pintype "passive"))
      (node (ref "U9") (pin "1") (pinfunction "1_1") (pintype "passive"))
    )
    (net (code "92") (name "Net-(R26-Pad2)") (class "Default")
      (node (ref "R26") (pin "2") (pinfunction "2_2") (pintype "passive"))
      (node (ref "U10") (pin "1") (pinfunction "1_1") (pintype "passive"))
    )
    (net (code "93") (name "Net-(R27-Pad2)") (class "Default")
      (node (ref "R27") (pin "2") (pinfunction "2_2") (pintype "passive"))
      (node (ref "U11") (pin "1") (pinfunction "1_1") (pintype "passive"))
    )
    (net (code "94") (name "Net-(R28-Pad2)") (class "Default")
      (node (ref "R28") (pin "2") (pinfunction "2_2") (pintype "passive"))
      (node (ref "U12") (pin "1") (pinfunction "1_1") (pintype "passive"))
    )
    (net (code "95") (name "Net-(R29-Pad2)") (class "Default")
      (node (ref "R29") (pin "2") (pinfunction "2_2") (pintype "passive"))
      (node (ref "U13") (pin "1") (pinfunction "1_1") (pintype "passive"))
    )
    (net (code "96") (name "Net-(R30-Pad2)") (class "Default")
      (node (ref "R30") (pin "2") (pinfunction "2_2") (pintype "passive"))
      (node (ref "U14") (pin "1") (pinfunction "1_1") (pintype "passive"))
    )
    (net (code "97") (name "Net-(R31-Pad2)") (class "Default")
      (node (ref "R31") (pin "2") (pinfunction "2_2") (pintype "passive"))
      (node (ref "U15") (pin "1") (pinfunction "1_1") (pintype "passive"))
    )
    (net (code "98") (name "Net-(R32-Pad2)") (class "Default")
      (node (ref "R32") (pin "2") (pinfunction "2_2") (pintype "passive"))
      (node (ref "U16") (pin "1") (pinfunction "1_1") (pintype "passive"))
    )
    (net (code "99") (name "VCC") (class "Default")
      (node (ref "P5") (pin "1") (pinfunction "1_1") (pintype "passive"))
      (node (ref "R33") (pin "2") (pinfunction "2_2") (pintype "passive"))
      (node (ref "R34") (pin "2") (pinfunction "2_2") (pintype "passive"))
      (node (ref "R35") (pin "2") (pinfunction "2_2") (pintype "passive"))
      (node (ref "R36") (pin "2") (pinfunction "2_2") (pintype "passive"))
      (node (ref "R37") (pin "2") (pinfunction "2_2") (pintype "passive"))
      (node (ref "R38") (pin "2") (pinfunction "2_2") (pintype "passive"))
      (node (ref "R39") (pin "2") (pinfunction "2_2") (pintype "passive"))
      (node (ref "R40") (pin "2") (pinfunction "2_2") (pintype "passive"))
      (node (ref "R41") (pin "2") (pinfunction "2_2") (pintype "passive"))
      (node (ref "R42") (pin "2") (pinfunction "2_2") (pintype "passive"))
      (node (ref "R43") (pin "2") (pinfunction "2_2") (pintype "passive"))
      (node (ref "R44") (pin "2") (pinfunction "2_2") (pintype "passive"))
      (node (ref "R45") (pin "2") (pinfunction "2_2") (pintype "passive"))
      (node (ref "R46") (pin "2") (pinfunction "2_2") (pintype "passive"))
      (node (ref "R47") (pin "2") (pinfunction "2_2") (pintype "passive"))
      (node (ref "R48") (pin "2") (pinfunction "2_2") (pintype "passive"))
      (node (ref "R49") (pin "1") (pinfunction "1_1") (pintype "passive"))
      (node (ref "R50") (pin "1") (pinfunction "1_1") (pintype "passive"))
      (node (ref "R51") (pin "1") (pinfunction "1_1") (pintype "passive"))
      (node (ref "R52") (pin "1") (pinfunction "1_1") (pintype "passive"))
      (node (ref "R53") (pin "1") (pinfunction "1_1") (pintype "passive"))
      (node (ref "R54") (pin "1") (pinfunction "1_1") (pintype "passive"))
      (node (ref "R55") (pin "1") (pinfunction "1_1") (pintype "passive"))
      (node (ref "R56") (pin "1") (pinfunction "1_1") (pintype "passive"))
      (node (ref "R57") (pin "1") (pinfunction "1_1") (pintype "passive"))
      (node (ref "R58") (pin "1") (pinfunction "1_1") (pintype "passive"))
      (node (ref "R59") (pin "1") (pinfunction "1_1") (pintype "passive"))
      (node (ref "R60") (pin "1") (pinfunction "1_1") (pintype "passive"))
      (node (ref "R61") (pin "1") (pinfunction "1_1") (pintype "passive"))
      (node (ref "R62") (pin "1") (pinfunction "1_1") (pintype "passive"))
      (node (ref "R63") (pin "1") (pinfunction "1_1") (pintype "passive"))
      (node (ref "R64") (pin "1") (pinfunction "1_1") (pintype "passive"))
      (node (ref "R65") (pin "2") (pinfunction "2_2") (pintype "passive"))
    )
  )
)
